# Scheme.net
KiCad netlist of a schematic drawn in Altium Designer
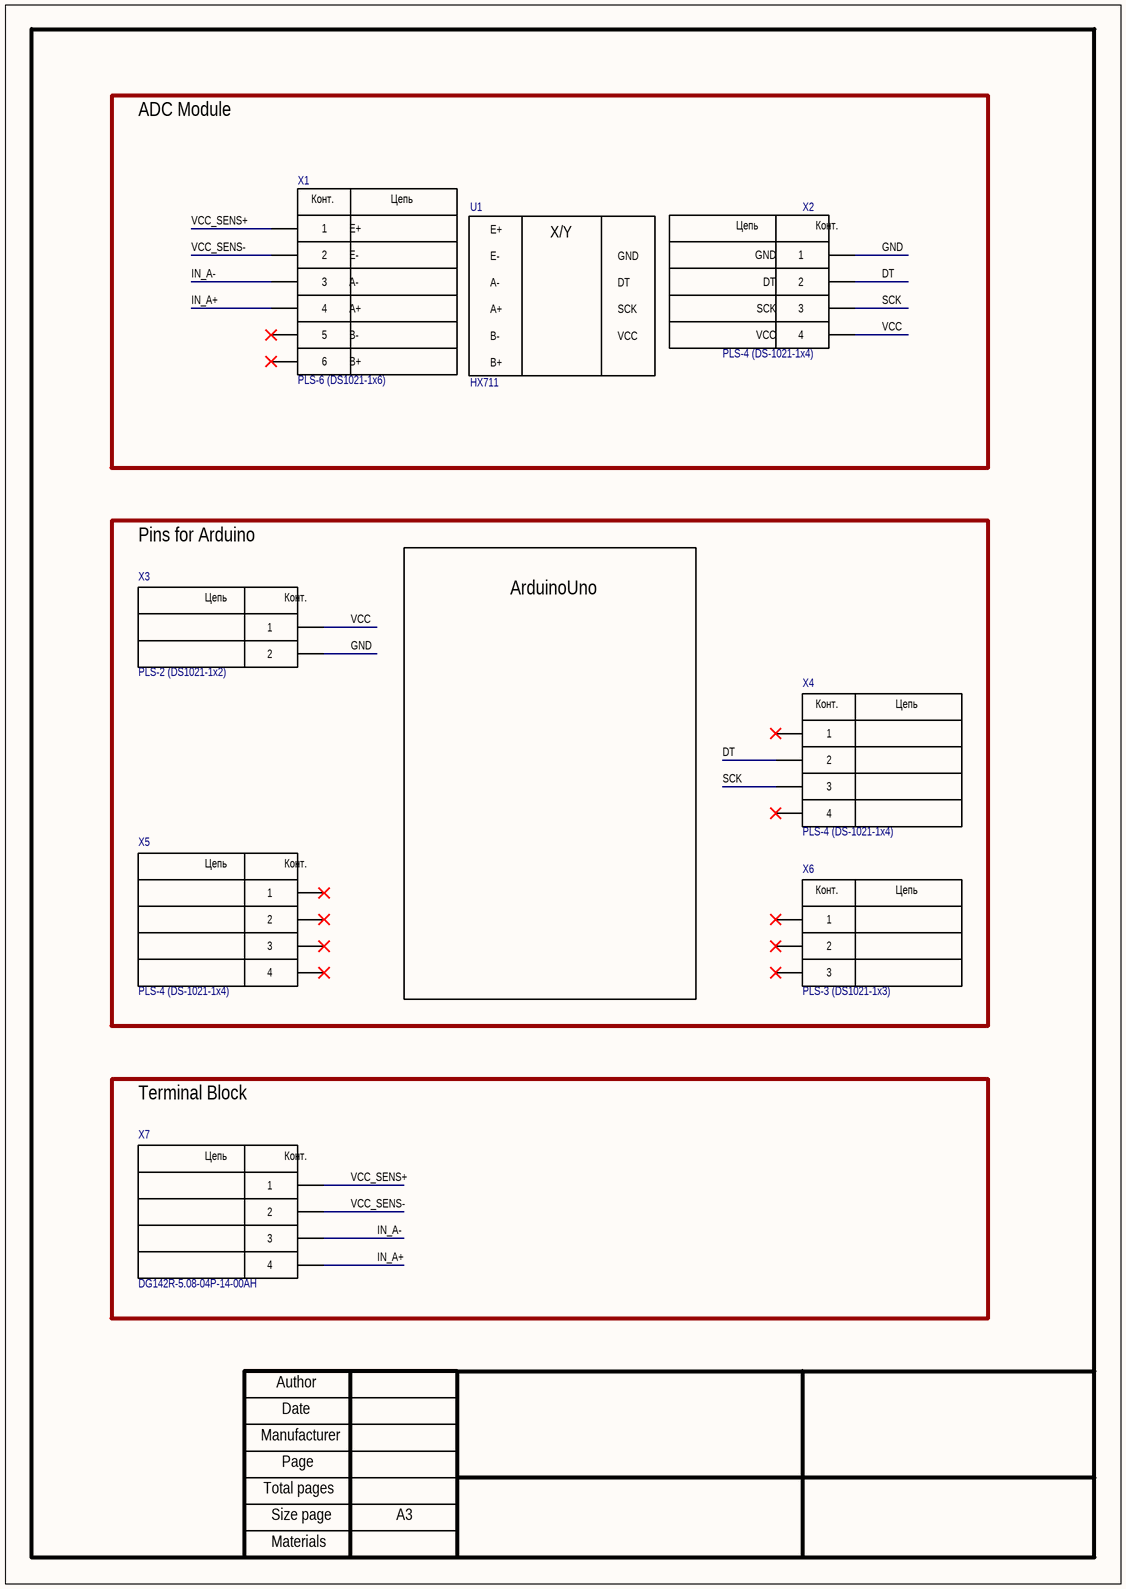
[diagram p0: Scheme.SchDoc]

(export (version "E")
  (design (tool "Eeschema 10.0.6"))
  (components
    (comp (ref "U1")
      (value "HX711")
      (footprint "EVALBRD:HX711")
      (description "ADC Module")
      (fields (field (name "MANUFACTURER") "OKYSTAR") (field (name "MANUFACTURER PART NUMBER") "8002691862"))
      (libsource (lib "EVALBRD") (part "HX711"))
    )
    (comp (ref "X1")
      (value "PLS-6 (DS1021-1x6)")
      (footprint "X:CON: PLS-6")
      (fields (field (name "MANUFACTURER") "Connfly electronic (Zhenqin)"))
      (libsource (lib "X") (part "6-Connector"))
    )
    (comp (ref "X2")
      (value "PLS-4 (DS-1021-1x4)")
      (footprint "X:CON: PLS-4")
      (fields (field (name "MANUFACTURER") "Connfly electronic (Zhenqin)"))
      (libsource (lib "X") (part "4-Connector"))
    )
    (comp (ref "X3")
      (value "PLS-2 (DS1021-1x2)")
      (footprint "X:CON: PLS-2")
      (fields (field (name "MANUFACTURER") "Connfly electronic (Zhenqin)"))
      (libsource (lib "X") (part "2-Connector"))
    )
    (comp (ref "X4")
      (value "PLS-4 (DS-1021-1x4)")
      (footprint "X:CON: PLS-4")
      (fields (field (name "MANUFACTURER") "Connfly electronic (Zhenqin)"))
      (libsource (lib "") (part "4-Connector_1"))
    )
    (comp (ref "X5")
      (value "PLS-4 (DS-1021-1x4)")
      (footprint "X:CON: PLS-4")
      (fields (field (name "MANUFACTURER") "Connfly electronic (Zhenqin)"))
      (libsource (lib "X") (part "4-Connector"))
    )
    (comp (ref "X6")
      (value "PLS-3 (DS1021-1x3)")
      (footprint "X:CON: PLS-3")
      (fields (field (name "MANUFACTURER") "Connfly electronic (Zhenqin)"))
      (libsource (lib "X") (part "3-Connector"))
    )
    (comp (ref "X7")
      (value "DG142R-5.08-04P-14-00AH")
      (footprint "X:CON: DG142V-5.08-4P")
      (fields (field (name "MANUFACTURER") "Degson Electronics"))
      (libsource (lib "") (part "4-Connector_2"))
    )
  )
  (nets
    (net (code "1") (name "/DT") (class "Default")
      (node (ref "X2") (pin "2") (pinfunction "DT________2_2") (pintype "passive"))
      (node (ref "X4") (pin "2") (pinfunction "2_2") (pintype "passive"))
    )
    (net (code "2") (name "/GND") (class "Default")
      (node (ref "X2") (pin "1") (pinfunction "GND________1_1") (pintype "passive"))
      (node (ref "X3") (pin "2") (pinfunction "2_2") (pintype "passive"))
    )
    (net (code "3") (name "/IN_A+") (class "Default")
      (node (ref "X1") (pin "4") (pinfunction "4________A+_4") (pintype "passive"))
      (node (ref "X7") (pin "4") (pinfunction "4_4") (pintype "passive"))
    )
    (net (code "4") (name "/IN_A-") (class "Default")
      (node (ref "X1") (pin "3") (pinfunction "3________A-_3") (pintype "passive"))
      (node (ref "X7") (pin "3") (pinfunction "3_3") (pintype "passive"))
    )
    (net (code "5") (name "/SCK") (class "Default")
      (node (ref "X2") (pin "3") (pinfunction "SCK________3_3") (pintype "passive"))
      (node (ref "X4") (pin "3") (pinfunction "3_3") (pintype "passive"))
    )
    (net (code "6") (name "/VCC") (class "Default")
      (node (ref "X2") (pin "4") (pinfunction "VCC________4_4") (pintype "passive"))
      (node (ref "X3") (pin "1") (pinfunction "1_1") (pintype "passive"))
    )
    (net (code "7") (name "/VCC_SENS+") (class "Default")
      (node (ref "X1") (pin "1") (pinfunction "1________E+_1") (pintype "passive"))
      (node (ref "X7") (pin "1") (pinfunction "1_1") (pintype "passive"))
    )
    (net (code "8") (name "/VCC_SENS-") (class "Default")
      (node (ref "X1") (pin "2") (pinfunction "2________E-_2") (pintype "passive"))
      (node (ref "X7") (pin "2") (pinfunction "2_2") (pintype "passive"))
    )
    (net (code "9") (name "unconnected-(X1-5________B--Pad5)") (class "Default")
      (node (ref "X1") (pin "5") (pinfunction "5________B-_5") (pintype "passive+no_connect"))
    )
    (net (code "10") (name "unconnected-(X1-6________B+-Pad6)") (class "Default")
      (node (ref "X1") (pin "6") (pinfunction "6________B+_6") (pintype "passive+no_connect"))
    )
    (net (code "11") (name "unconnected-(X4-Pad1)") (class "Default")
      (node (ref "X4") (pin "1") (pinfunction "1_1") (pintype "passive+no_connect"))
    )
    (net (code "12") (name "unconnected-(X4-Pad4)") (class "Default")
      (node (ref "X4") (pin "4") (pinfunction "4_4") (pintype "passive+no_connect"))
    )
    (net (code "13") (name "unconnected-(X5-DT________2-Pad2)") (class "Default")
      (node (ref "X5") (pin "2") (pinfunction "DT________2_2") (pintype "passive+no_connect"))
    )
    (net (code "14") (name "unconnected-(X5-GND________1-Pad1)") (class "Default")
      (node (ref "X5") (pin "1") (pinfunction "GND________1_1") (pintype "passive+no_connect"))
    )
    (net (code "15") (name "unconnected-(X5-SCK________3-Pad3)") (class "Default")
      (node (ref "X5") (pin "3") (pinfunction "SCK________3_3") (pintype "passive+no_connect"))
    )
    (net (code "16") (name "unconnected-(X5-VCC________4-Pad4)") (class "Default")
      (node (ref "X5") (pin "4") (pinfunction "VCC________4_4") (pintype "passive+no_connect"))
    )
    (net (code "17") (name "unconnected-(X6-Pad1)") (class "Default")
      (node (ref "X6") (pin "1") (pinfunction "1_1") (pintype "passive+no_connect"))
    )
    (net (code "18") (name "unconnected-(X6-Pad2)") (class "Default")
      (node (ref "X6") (pin "2") (pinfunction "2_2") (pintype "passive+no_connect"))
    )
    (net (code "19") (name "unconnected-(X6-Pad3)") (class "Default")
      (node (ref "X6") (pin "3") (pinfunction "3_3") (pintype "passive+no_connect"))
    )
  )
)
